# memoryboard2.net
KiCad netlist of a schematic drawn in EAGLE
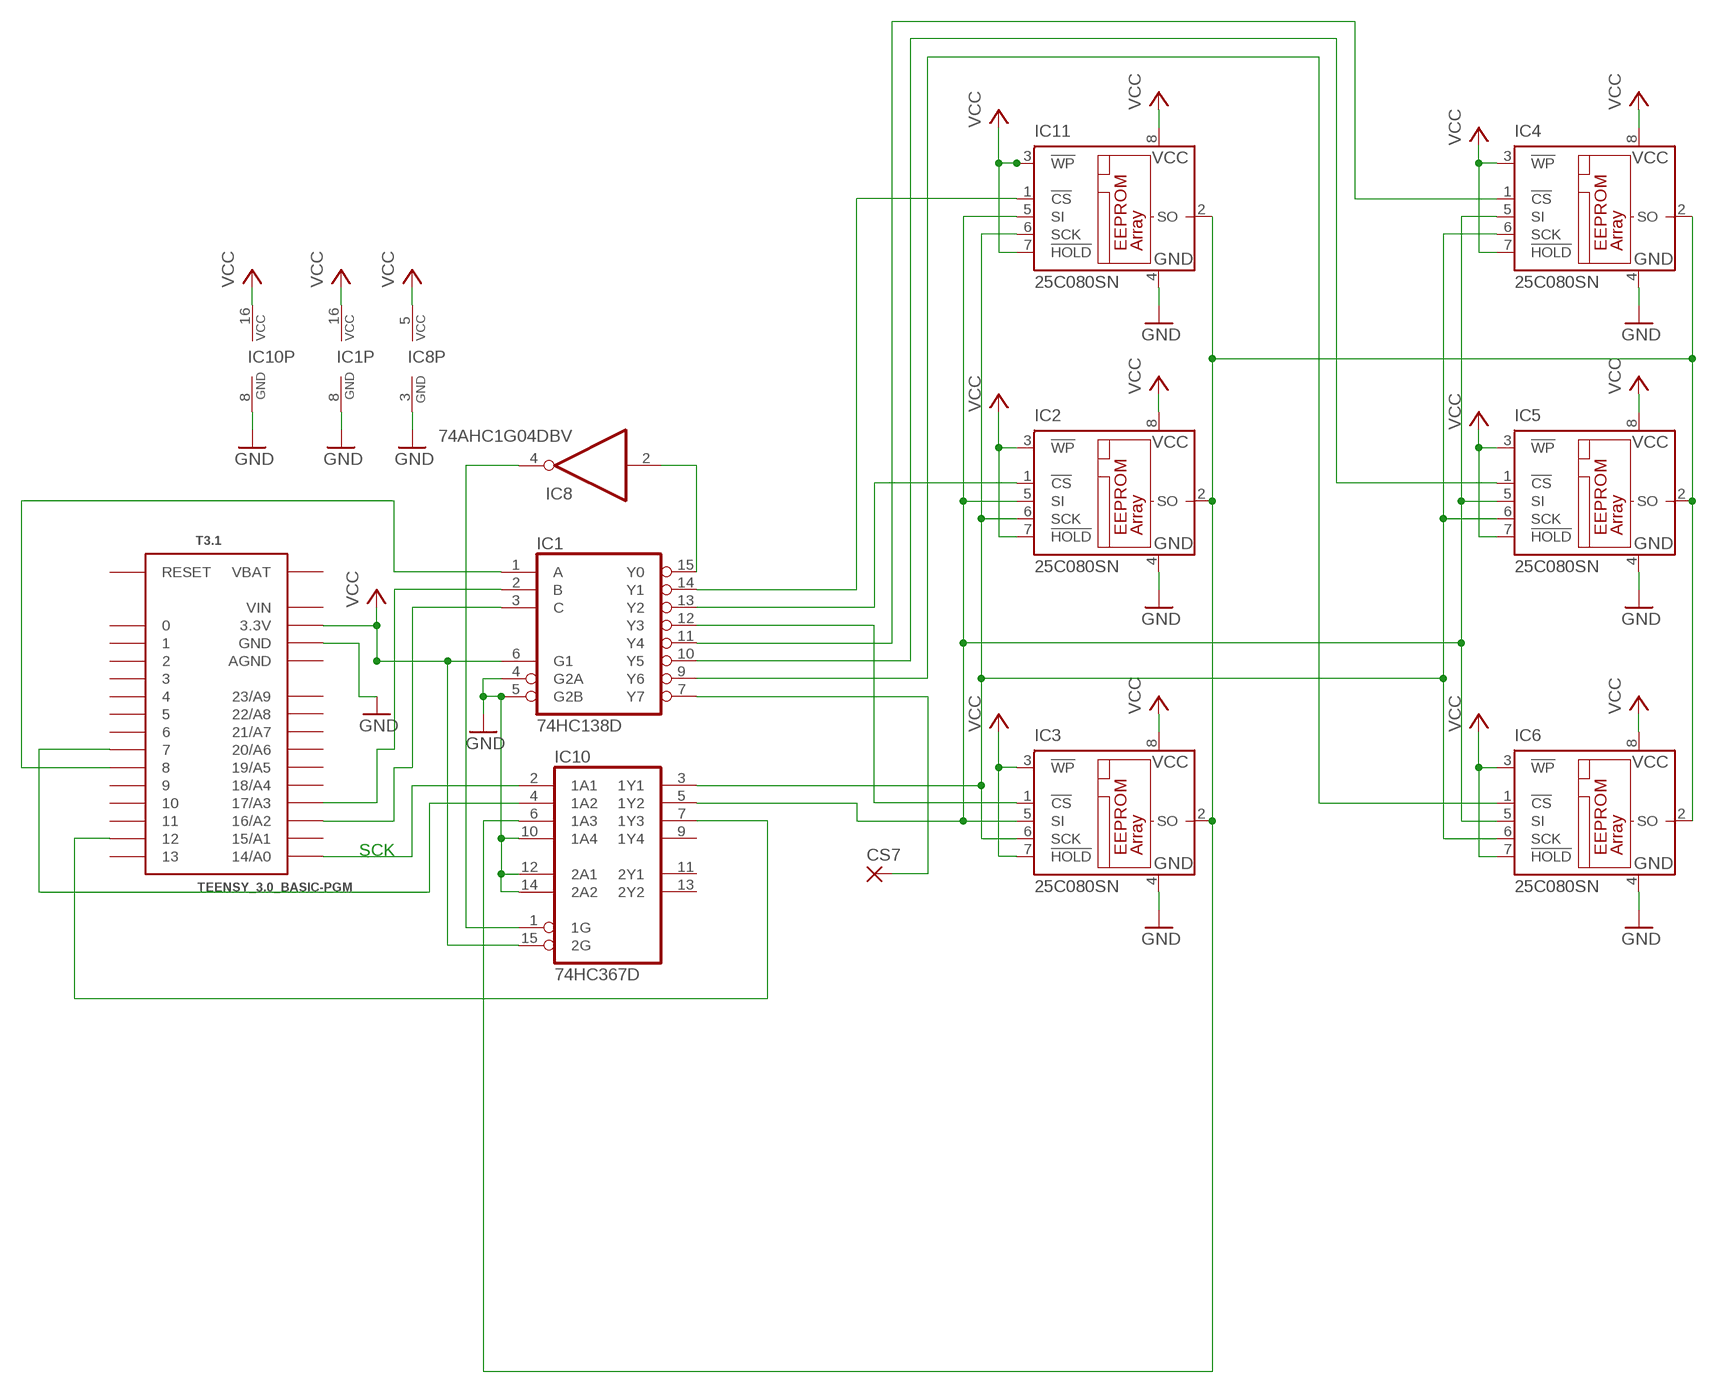
[diagram p0: schematic, sheet 1]

(export (version "E")
  (design (tool "Eeschema 10.0.6"))
  (components
    (comp (ref "CS7")
      (value "SMD2")
      (footprint "eagle-import:SMD1,27-2,54")
      (libsource (lib "eagle-import") (part "SMD2"))
    )
    (comp (ref "IC1")
      (value "74HC138D")
      (footprint "eagle-import:SO16")
      (libsource (lib "eagle-import") (part "74138DHC"))
    )
    (comp (ref "IC2")
      (value "25C080SN")
      (footprint "eagle-import:SO-08")
      (fields (field (name "MF") "MICROCHIP") (field (name "MPN") "25C080/SN"))
      (libsource (lib "eagle-import") (part "25SNC080"))
    )
    (comp (ref "IC3")
      (value "25C080SN")
      (footprint "eagle-import:SO-08")
      (fields (field (name "MF") "MICROCHIP") (field (name "MPN") "25C080/SN"))
      (libsource (lib "eagle-import") (part "25SNC080"))
    )
    (comp (ref "IC4")
      (value "25C080SN")
      (footprint "eagle-import:SO-08")
      (fields (field (name "MF") "MICROCHIP") (field (name "MPN") "25C080/SN"))
      (libsource (lib "eagle-import") (part "25SNC080"))
    )
    (comp (ref "IC5")
      (value "25C080SN")
      (footprint "eagle-import:SO-08")
      (fields (field (name "MF") "MICROCHIP") (field (name "MPN") "25C080/SN"))
      (libsource (lib "eagle-import") (part "25SNC080"))
    )
    (comp (ref "IC6")
      (value "25C080SN")
      (footprint "eagle-import:SO-08")
      (fields (field (name "MF") "MICROCHIP") (field (name "MPN") "25C080/SN"))
      (libsource (lib "eagle-import") (part "25SNC080"))
    )
    (comp (ref "IC8")
      (value "74AHC1G04DBV")
      (footprint "eagle-import:SOT23-5")
      (libsource (lib "eagle-import") (part "741G04DBVAHC"))
    )
    (comp (ref "IC10")
      (value "74HC367D")
      (footprint "eagle-import:SO16")
      (libsource (lib "eagle-import") (part "74367DHC"))
    )
    (comp (ref "IC11")
      (value "25C080SN")
      (footprint "eagle-import:SO-08")
      (fields (field (name "MF") "MICROCHIP") (field (name "MPN") "25C080/SN"))
      (libsource (lib "eagle-import") (part "25SNC080"))
    )
    (comp (ref "T3.1")
      (value "TEENSY_3.0_BASIC-PGM")
      (footprint "eagle-import:TEENSY_3.0_BASIC-PGM")
      (libsource (lib "eagle-import") (part "TEENSY_3.0_BASIC-PGM"))
    )
  )
  (nets
    (net (code "1") (name "/AGND") (class "Default")
      (node (ref "T3.1") (pin "AGND") (pinfunction "AGND_AGND") (pintype "power_in"))
    )
    (net (code "2") (name "/VBAT") (class "Default")
      (node (ref "T3.1") (pin "VBAT") (pinfunction "VBAT_VBAT") (pintype "power_in"))
    )
    (net (code "3") (name "/VIN") (class "Default")
      (node (ref "T3.1") (pin "VIN") (pinfunction "VIN_VIN") (pintype "power_in"))
    )
    (net (code "4") (name "GND") (class "Default")
      (node (ref "IC1") (pin "4") (pinfunction "G2A_4") (pintype "input"))
      (node (ref "IC1") (pin "5") (pinfunction "G2B_5") (pintype "input"))
      (node (ref "IC1") (pin "8") (pinfunction "GND_8") (pintype "power_in"))
      (node (ref "IC10") (pin "10") (pinfunction "1A4_10") (pintype "input"))
      (node (ref "IC10") (pin "12") (pinfunction "2A1_12") (pintype "input"))
      (node (ref "IC10") (pin "14") (pinfunction "2A2_14") (pintype "input"))
      (node (ref "IC10") (pin "8") (pinfunction "GND_8") (pintype "power_in"))
      (node (ref "IC11") (pin "4") (pinfunction "GND_4") (pintype "power_in"))
      (node (ref "IC2") (pin "4") (pinfunction "GND_4") (pintype "power_in"))
      (node (ref "IC3") (pin "4") (pinfunction "GND_4") (pintype "power_in"))
      (node (ref "IC4") (pin "4") (pinfunction "GND_4") (pintype "power_in"))
      (node (ref "IC5") (pin "4") (pinfunction "GND_4") (pintype "power_in"))
      (node (ref "IC6") (pin "4") (pinfunction "GND_4") (pintype "power_in"))
      (node (ref "IC8") (pin "3") (pinfunction "GND_3") (pintype "power_in"))
      (node (ref "T3.1") (pin "GND") (pinfunction "GND_GND") (pintype "power_in"))
      (node (ref "T3.1") (pin "GND1") (pinfunction "GND_GND1") (pintype "power_in"))
    )
    (net (code "5") (name "Net-(CS7-P)") (class "Default")
      (node (ref "CS7") (pin "1") (pinfunction "P_1") (pintype "passive"))
      (node (ref "IC1") (pin "7") (pinfunction "Y7_7") (pintype "output"))
    )
    (net (code "6") (name "Net-(IC1A-A)") (class "Default")
      (node (ref "IC1") (pin "1") (pinfunction "A_1") (pintype "input"))
      (node (ref "T3.1") (pin "8") (pinfunction "8_8") (pintype "bidirectional"))
    )
    (net (code "7") (name "Net-(IC1A-B)") (class "Default")
      (node (ref "IC1") (pin "2") (pinfunction "B_2") (pintype "input"))
      (node (ref "T3.1") (pin "17/A3") (pinfunction "17/A3_17/A3") (pintype "bidirectional"))
    )
    (net (code "8") (name "Net-(IC1A-C)") (class "Default")
      (node (ref "IC1") (pin "3") (pinfunction "C_3") (pintype "input"))
      (node (ref "T3.1") (pin "16/A2") (pinfunction "16/A2_16/A2") (pintype "bidirectional"))
    )
    (net (code "9") (name "Net-(IC1A-Y0)") (class "Default")
      (node (ref "IC1") (pin "15") (pinfunction "Y0_15") (pintype "output"))
      (node (ref "IC8") (pin "2") (pinfunction "I_2") (pintype "input"))
    )
    (net (code "10") (name "Net-(IC1A-Y2)") (class "Default")
      (node (ref "IC1") (pin "13") (pinfunction "Y2_13") (pintype "output"))
      (node (ref "IC2") (pin "1") (pinfunction "~{CS}_1") (pintype "input"))
    )
    (net (code "11") (name "Net-(IC1A-Y3)") (class "Default")
      (node (ref "IC1") (pin "12") (pinfunction "Y3_12") (pintype "output"))
      (node (ref "IC3") (pin "1") (pinfunction "~{CS}_1") (pintype "input"))
    )
    (net (code "12") (name "Net-(IC1A-Y4)") (class "Default")
      (node (ref "IC1") (pin "11") (pinfunction "Y4_11") (pintype "output"))
      (node (ref "IC4") (pin "1") (pinfunction "~{CS}_1") (pintype "input"))
    )
    (net (code "13") (name "Net-(IC1A-Y5)") (class "Default")
      (node (ref "IC1") (pin "10") (pinfunction "Y5_10") (pintype "output"))
      (node (ref "IC5") (pin "1") (pinfunction "~{CS}_1") (pintype "input"))
    )
    (net (code "14") (name "Net-(IC1A-Y6)") (class "Default")
      (node (ref "IC1") (pin "9") (pinfunction "Y6_9") (pintype "output"))
      (node (ref "IC6") (pin "1") (pinfunction "~{CS}_1") (pintype "input"))
    )
    (net (code "15") (name "Net-(IC10A-1A1)") (class "Default")
      (node (ref "IC10") (pin "2") (pinfunction "1A1_2") (pintype "input"))
      (node (ref "T3.1") (pin "14/A0") (pinfunction "14/A0_14/A0") (pintype "bidirectional"))
    )
    (net (code "16") (name "Net-(IC10A-1A2)") (class "Default")
      (node (ref "IC10") (pin "4") (pinfunction "1A2_4") (pintype "input"))
      (node (ref "T3.1") (pin "7") (pinfunction "7_7") (pintype "bidirectional"))
    )
    (net (code "17") (name "Net-(IC10A-1A3)") (class "Default")
      (node (ref "IC10") (pin "6") (pinfunction "1A3_6") (pintype "input"))
      (node (ref "IC11") (pin "2") (pinfunction "SO_2") (pintype "bidirectional"))
      (node (ref "IC2") (pin "2") (pinfunction "SO_2") (pintype "bidirectional"))
      (node (ref "IC3") (pin "2") (pinfunction "SO_2") (pintype "bidirectional"))
      (node (ref "IC4") (pin "2") (pinfunction "SO_2") (pintype "bidirectional"))
      (node (ref "IC5") (pin "2") (pinfunction "SO_2") (pintype "bidirectional"))
      (node (ref "IC6") (pin "2") (pinfunction "SO_2") (pintype "bidirectional"))
    )
    (net (code "18") (name "Net-(IC10A-1G)") (class "Default")
      (node (ref "IC10") (pin "1") (pinfunction "1G_1") (pintype "input"))
      (node (ref "IC8") (pin "4") (pinfunction "O_4") (pintype "output"))
    )
    (net (code "19") (name "Net-(IC10A-1Y1)") (class "Default")
      (node (ref "IC10") (pin "3") (pinfunction "1Y1_3") (pintype "tri_state"))
      (node (ref "IC11") (pin "6") (pinfunction "SCK_6") (pintype "input"))
      (node (ref "IC2") (pin "6") (pinfunction "SCK_6") (pintype "input"))
      (node (ref "IC3") (pin "6") (pinfunction "SCK_6") (pintype "input"))
      (node (ref "IC4") (pin "6") (pinfunction "SCK_6") (pintype "input"))
      (node (ref "IC5") (pin "6") (pinfunction "SCK_6") (pintype "input"))
      (node (ref "IC6") (pin "6") (pinfunction "SCK_6") (pintype "input"))
    )
    (net (code "20") (name "Net-(IC10A-1Y2)") (class "Default")
      (node (ref "IC10") (pin "5") (pinfunction "1Y2_5") (pintype "tri_state"))
      (node (ref "IC11") (pin "5") (pinfunction "SI_5") (pintype "input"))
      (node (ref "IC2") (pin "5") (pinfunction "SI_5") (pintype "input"))
      (node (ref "IC3") (pin "5") (pinfunction "SI_5") (pintype "input"))
      (node (ref "IC4") (pin "5") (pinfunction "SI_5") (pintype "input"))
      (node (ref "IC5") (pin "5") (pinfunction "SI_5") (pintype "input"))
      (node (ref "IC6") (pin "5") (pinfunction "SI_5") (pintype "input"))
    )
    (net (code "21") (name "Net-(IC10A-1Y3)") (class "Default")
      (node (ref "IC10") (pin "7") (pinfunction "1Y3_7") (pintype "tri_state"))
      (node (ref "T3.1") (pin "12") (pinfunction "12_12") (pintype "bidirectional"))
    )
    (net (code "22") (name "Net-(IC11-~{CS})") (class "Default")
      (node (ref "IC1") (pin "14") (pinfunction "Y1_14") (pintype "output"))
      (node (ref "IC11") (pin "1") (pinfunction "~{CS}_1") (pintype "input"))
    )
    (net (code "23") (name "VCC") (class "Default")
      (node (ref "IC1") (pin "16") (pinfunction "VCC_16") (pintype "power_in"))
      (node (ref "IC1") (pin "6") (pinfunction "G1_6") (pintype "input"))
      (node (ref "IC10") (pin "15") (pinfunction "2G_15") (pintype "input"))
      (node (ref "IC10") (pin "16") (pinfunction "VCC_16") (pintype "power_in"))
      (node (ref "IC11") (pin "3") (pinfunction "~{WP}_3") (pintype "input"))
      (node (ref "IC11") (pin "7") (pinfunction "~{HOLD}_7") (pintype "input"))
      (node (ref "IC11") (pin "8") (pinfunction "VCC_8") (pintype "power_in"))
      (node (ref "IC2") (pin "3") (pinfunction "~{WP}_3") (pintype "input"))
      (node (ref "IC2") (pin "7") (pinfunction "~{HOLD}_7") (pintype "input"))
      (node (ref "IC2") (pin "8") (pinfunction "VCC_8") (pintype "power_in"))
      (node (ref "IC3") (pin "3") (pinfunction "~{WP}_3") (pintype "input"))
      (node (ref "IC3") (pin "7") (pinfunction "~{HOLD}_7") (pintype "input"))
      (node (ref "IC3") (pin "8") (pinfunction "VCC_8") (pintype "power_in"))
      (node (ref "IC4") (pin "3") (pinfunction "~{WP}_3") (pintype "input"))
      (node (ref "IC4") (pin "7") (pinfunction "~{HOLD}_7") (pintype "input"))
      (node (ref "IC4") (pin "8") (pinfunction "VCC_8") (pintype "power_in"))
      (node (ref "IC5") (pin "3") (pinfunction "~{WP}_3") (pintype "input"))
      (node (ref "IC5") (pin "7") (pinfunction "~{HOLD}_7") (pintype "input"))
      (node (ref "IC5") (pin "8") (pinfunction "VCC_8") (pintype "power_in"))
      (node (ref "IC6") (pin "3") (pinfunction "~{WP}_3") (pintype "input"))
      (node (ref "IC6") (pin "7") (pinfunction "~{HOLD}_7") (pintype "input"))
      (node (ref "IC6") (pin "8") (pinfunction "VCC_8") (pintype "power_in"))
      (node (ref "IC8") (pin "5") (pinfunction "VCC_5") (pintype "power_in"))
      (node (ref "T3.1") (pin "3.3V") (pinfunction "3.3V_3.3V") (pintype "power_in"))
      (node (ref "T3.1") (pin "3.3V1") (pinfunction "3.3V_3.3V1") (pintype "power_in"))
    )
    (net (code "24") (name "unconnected-(IC10A-1Y4-Pad9)") (class "Default")
      (node (ref "IC10") (pin "9") (pinfunction "1Y4_9") (pintype "tri_state"))
    )
    (net (code "25") (name "unconnected-(IC10A-2Y1-Pad11)") (class "Default")
      (node (ref "IC10") (pin "11") (pinfunction "2Y1_11") (pintype "tri_state"))
    )
    (net (code "26") (name "unconnected-(IC10A-2Y2-Pad13)") (class "Default")
      (node (ref "IC10") (pin "13") (pinfunction "2Y2_13") (pintype "tri_state"))
    )
    (net (code "27") (name "unconnected-(T3.1-Pad0)") (class "Default")
      (node (ref "T3.1") (pin "0") (pinfunction "0_0") (pintype "bidirectional"))
    )
    (net (code "28") (name "unconnected-(T3.1-Pad1)") (class "Default")
      (node (ref "T3.1") (pin "1") (pinfunction "1_1") (pintype "bidirectional"))
    )
    (net (code "29") (name "unconnected-(T3.1-Pad2)") (class "Default")
      (node (ref "T3.1") (pin "2") (pinfunction "2_2") (pintype "bidirectional"))
    )
    (net (code "30") (name "unconnected-(T3.1-Pad3)") (class "Default")
      (node (ref "T3.1") (pin "3") (pinfunction "3_3") (pintype "bidirectional"))
    )
    (net (code "31") (name "unconnected-(T3.1-Pad4)") (class "Default")
      (node (ref "T3.1") (pin "4") (pinfunction "4_4") (pintype "bidirectional"))
    )
    (net (code "32") (name "unconnected-(T3.1-Pad5)") (class "Default")
      (node (ref "T3.1") (pin "5") (pinfunction "5_5") (pintype "bidirectional"))
    )
    (net (code "33") (name "unconnected-(T3.1-Pad6)") (class "Default")
      (node (ref "T3.1") (pin "6") (pinfunction "6_6") (pintype "bidirectional"))
    )
    (net (code "34") (name "unconnected-(T3.1-Pad9)") (class "Default")
      (node (ref "T3.1") (pin "9") (pinfunction "9_9") (pintype "bidirectional"))
    )
    (net (code "35") (name "unconnected-(T3.1-Pad10)") (class "Default")
      (node (ref "T3.1") (pin "10") (pinfunction "10_10") (pintype "bidirectional"))
    )
    (net (code "36") (name "unconnected-(T3.1-Pad11)") (class "Default")
      (node (ref "T3.1") (pin "11") (pinfunction "11_11") (pintype "bidirectional"))
    )
    (net (code "37") (name "unconnected-(T3.1-Pad13)") (class "Default")
      (node (ref "T3.1") (pin "13") (pinfunction "13_13") (pintype "bidirectional"))
    )
    (net (code "38") (name "unconnected-(T3.1-Pad15{slash}A1)") (class "Default")
      (node (ref "T3.1") (pin "15/A1") (pinfunction "15/A1_15/A1") (pintype "bidirectional"))
    )
    (net (code "39") (name "unconnected-(T3.1-Pad18{slash}A4)") (class "Default")
      (node (ref "T3.1") (pin "18/A4") (pinfunction "18/A4_18/A4") (pintype "bidirectional"))
    )
    (net (code "40") (name "unconnected-(T3.1-Pad19{slash}A5)") (class "Default")
      (node (ref "T3.1") (pin "19/A5") (pinfunction "19/A5_19/A5") (pintype "bidirectional"))
    )
    (net (code "41") (name "unconnected-(T3.1-Pad20{slash}A6)") (class "Default")
      (node (ref "T3.1") (pin "20/A6") (pinfunction "20/A6_20/A6") (pintype "bidirectional"))
    )
    (net (code "42") (name "unconnected-(T3.1-Pad21{slash}A7)") (class "Default")
      (node (ref "T3.1") (pin "21/A7") (pinfunction "21/A7_21/A7") (pintype "bidirectional"))
    )
    (net (code "43") (name "unconnected-(T3.1-Pad22{slash}A8)") (class "Default")
      (node (ref "T3.1") (pin "22/A8") (pinfunction "22/A8_22/A8") (pintype "bidirectional"))
    )
    (net (code "44") (name "unconnected-(T3.1-Pad23{slash}A9)") (class "Default")
      (node (ref "T3.1") (pin "23/A9") (pinfunction "23/A9_23/A9") (pintype "bidirectional"))
    )
    (net (code "45") (name "unconnected-(T3.1-PadRESET)") (class "Default")
      (node (ref "T3.1") (pin "RESET") (pinfunction "RESET_RESET") (pintype "bidirectional"))
    )
  )
)
